# sidecar.net
KiCad netlist of a schematic drawn in EAGLE
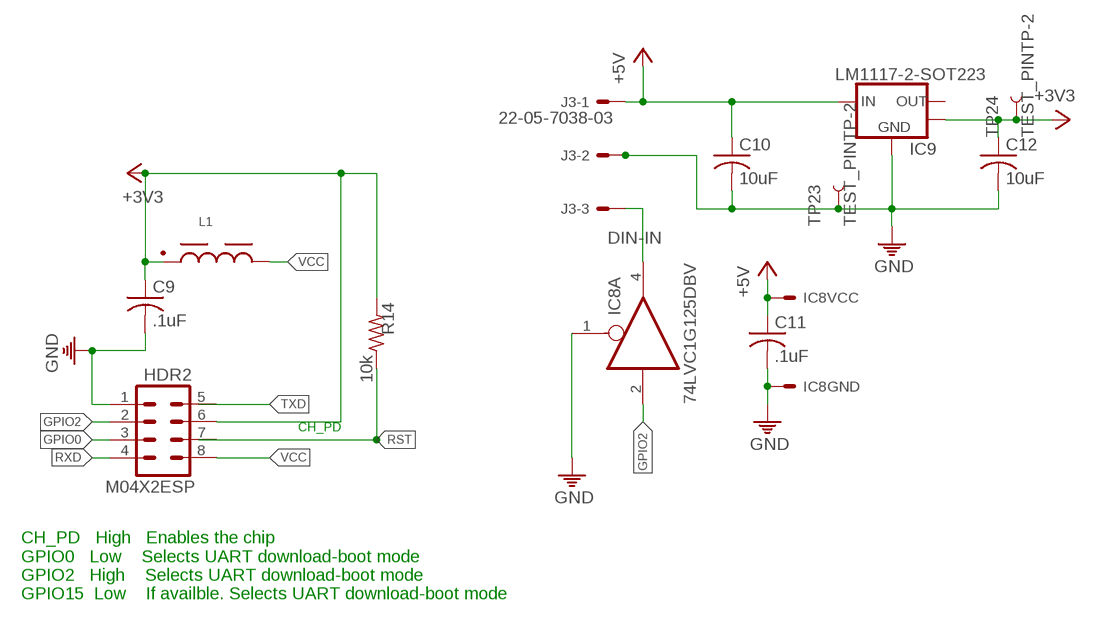
[diagram p0: schematic, sheet 1]

(export (version "E")
  (design (tool "Eeschema 10.0.6"))
  (components
    (comp (ref "C9")
      (value ".1uF")
      (footprint "eagle-import:C0805")
      (libsource (lib "eagle-import") (part "C-USC0805"))
    )
    (comp (ref "C10")
      (value "10uF")
      (footprint "eagle-import:C0805")
      (libsource (lib "eagle-import") (part "C-USC0805"))
    )
    (comp (ref "C11")
      (value ".1uF")
      (footprint "eagle-import:C0805")
      (libsource (lib "eagle-import") (part "C-USC0805"))
    )
    (comp (ref "C12")
      (value "10uF")
      (footprint "eagle-import:C0805")
      (libsource (lib "eagle-import") (part "C-USC0805"))
    )
    (comp (ref "HDR2")
      (value "M04X2ESP")
      (footprint "eagle-import:2X4-ESP")
      (libsource (lib "eagle-import") (part "M04X2ESP"))
    )
    (comp (ref "IC8")
      (value "74LVC1G125DBV")
      (footprint "eagle-import:SOT23-5")
      (libsource (lib "eagle-import") (part "741G125DBVLVC"))
    )
    (comp (ref "IC9")
      (value "LM1117-2-SOT223")
      (footprint "eagle-import:SOT-223-3")
      (libsource (lib "eagle-import") (part "LM1117-2-SOT223"))
    )
    (comp (ref "J3")
      (value "22-05-7038-03")
      (footprint "eagle-import:7395-03")
      (fields (field (name "MF") "MOLEX"))
      (libsource (lib "eagle-import") (part "22-?-0305-7038"))
    )
    (comp (ref "L1")
      (value "WE-CBA_0805_782851102_WB/HS")
      (footprint "eagle-import:WE-CBA_0805(W=3)")
      (libsource (lib "eagle-import") (part "WE-CBA_0805_WB/HS_782851102"))
    )
    (comp (ref "R14")
      (value "10k")
      (footprint "eagle-import:R0805")
      (libsource (lib "eagle-import") (part "R-US_R0805"))
    )
    (comp (ref "TP23")
      (value "TEST_PINTP-2")
      (footprint "eagle-import:TP-2")
      (libsource (lib "eagle-import") (part "TEST_PINTP-2"))
    )
    (comp (ref "TP24")
      (value "TEST_PINTP-2")
      (footprint "eagle-import:TP-2")
      (libsource (lib "eagle-import") (part "TEST_PINTP-2"))
    )
  )
  (nets
    (net (code "1") (name "+3V3") (class "Default")
      (node (ref "C12") (pin "1") (pinfunction "1_1") (pintype "passive"))
      (node (ref "C9") (pin "1") (pinfunction "1_1") (pintype "passive"))
      (node (ref "HDR2") (pin "6") (pinfunction "6_6") (pintype "passive"))
      (node (ref "IC9") (pin "4") (pinfunction "HEATSINK_4") (pintype "bidirectional"))
      (node (ref "L1") (pin "1") (pinfunction "1_1") (pintype "passive"))
      (node (ref "R14") (pin "2") (pinfunction "2_2") (pintype "passive"))
      (node (ref "TP24") (pin "P$1") (pinfunction "1_P$1") (pintype "bidirectional"))
    )
    (net (code "2") (name "+5V") (class "Default")
      (node (ref "C10") (pin "1") (pinfunction "1_1") (pintype "passive"))
      (node (ref "C11") (pin "1") (pinfunction "1_1") (pintype "passive"))
      (node (ref "IC8") (pin "5") (pinfunction "S_5") (pintype "passive"))
      (node (ref "IC9") (pin "3") (pinfunction "VIN_3") (pintype "bidirectional"))
      (node (ref "J3") (pin "1") (pinfunction "S_1") (pintype "passive"))
    )
    (net (code "3") (name "/DIN-IN") (class "Default")
      (node (ref "IC8") (pin "4") (pinfunction "O_4") (pintype "tri_state"))
      (node (ref "J3") (pin "3") (pinfunction "S_3") (pintype "passive"))
    )
    (net (code "4") (name "GND") (class "Default")
      (node (ref "C10") (pin "2") (pinfunction "2_2") (pintype "passive"))
      (node (ref "C11") (pin "2") (pinfunction "2_2") (pintype "passive"))
      (node (ref "C12") (pin "2") (pinfunction "2_2") (pintype "passive"))
      (node (ref "C9") (pin "2") (pinfunction "2_2") (pintype "passive"))
      (node (ref "HDR2") (pin "1") (pinfunction "1_1") (pintype "passive"))
      (node (ref "IC8") (pin "1") (pinfunction "OE_1") (pintype "input"))
      (node (ref "IC8") (pin "3") (pinfunction "S_3") (pintype "passive"))
      (node (ref "IC9") (pin "1") (pinfunction "GND_1") (pintype "bidirectional"))
      (node (ref "J3") (pin "2") (pinfunction "S_2") (pintype "passive"))
      (node (ref "TP23") (pin "P$1") (pinfunction "1_P$1") (pintype "bidirectional"))
    )
    (net (code "5") (name "GPIO0") (class "Default")
      (node (ref "HDR2") (pin "3") (pinfunction "3_3") (pintype "passive"))
    )
    (net (code "6") (name "GPIO2") (class "Default")
      (node (ref "HDR2") (pin "2") (pinfunction "2_2") (pintype "passive"))
      (node (ref "IC8") (pin "2") (pinfunction "I_2") (pintype "input"))
    )
    (net (code "7") (name "RST") (class "Default")
      (node (ref "HDR2") (pin "7") (pinfunction "7_7") (pintype "passive"))
      (node (ref "R14") (pin "1") (pinfunction "1_1") (pintype "passive"))
    )
    (net (code "8") (name "RXD") (class "Default")
      (node (ref "HDR2") (pin "4") (pinfunction "4_4") (pintype "passive"))
    )
    (net (code "9") (name "TXD") (class "Default")
      (node (ref "HDR2") (pin "5") (pinfunction "5_5") (pintype "passive"))
    )
    (net (code "10") (name "VCC") (class "Default")
      (node (ref "HDR2") (pin "8") (pinfunction "8_8") (pintype "passive"))
      (node (ref "L1") (pin "2") (pinfunction "2_2") (pintype "passive"))
    )
    (net (code "11") (name "unconnected-(IC9-VOUT-Pad2)") (class "Default")
      (node (ref "IC9") (pin "2") (pinfunction "VOUT_2") (pintype "bidirectional"))
    )
  )
)
